# Sedna_Power_Board_v2.net
KiCad netlist of a schematic drawn in EAGLE
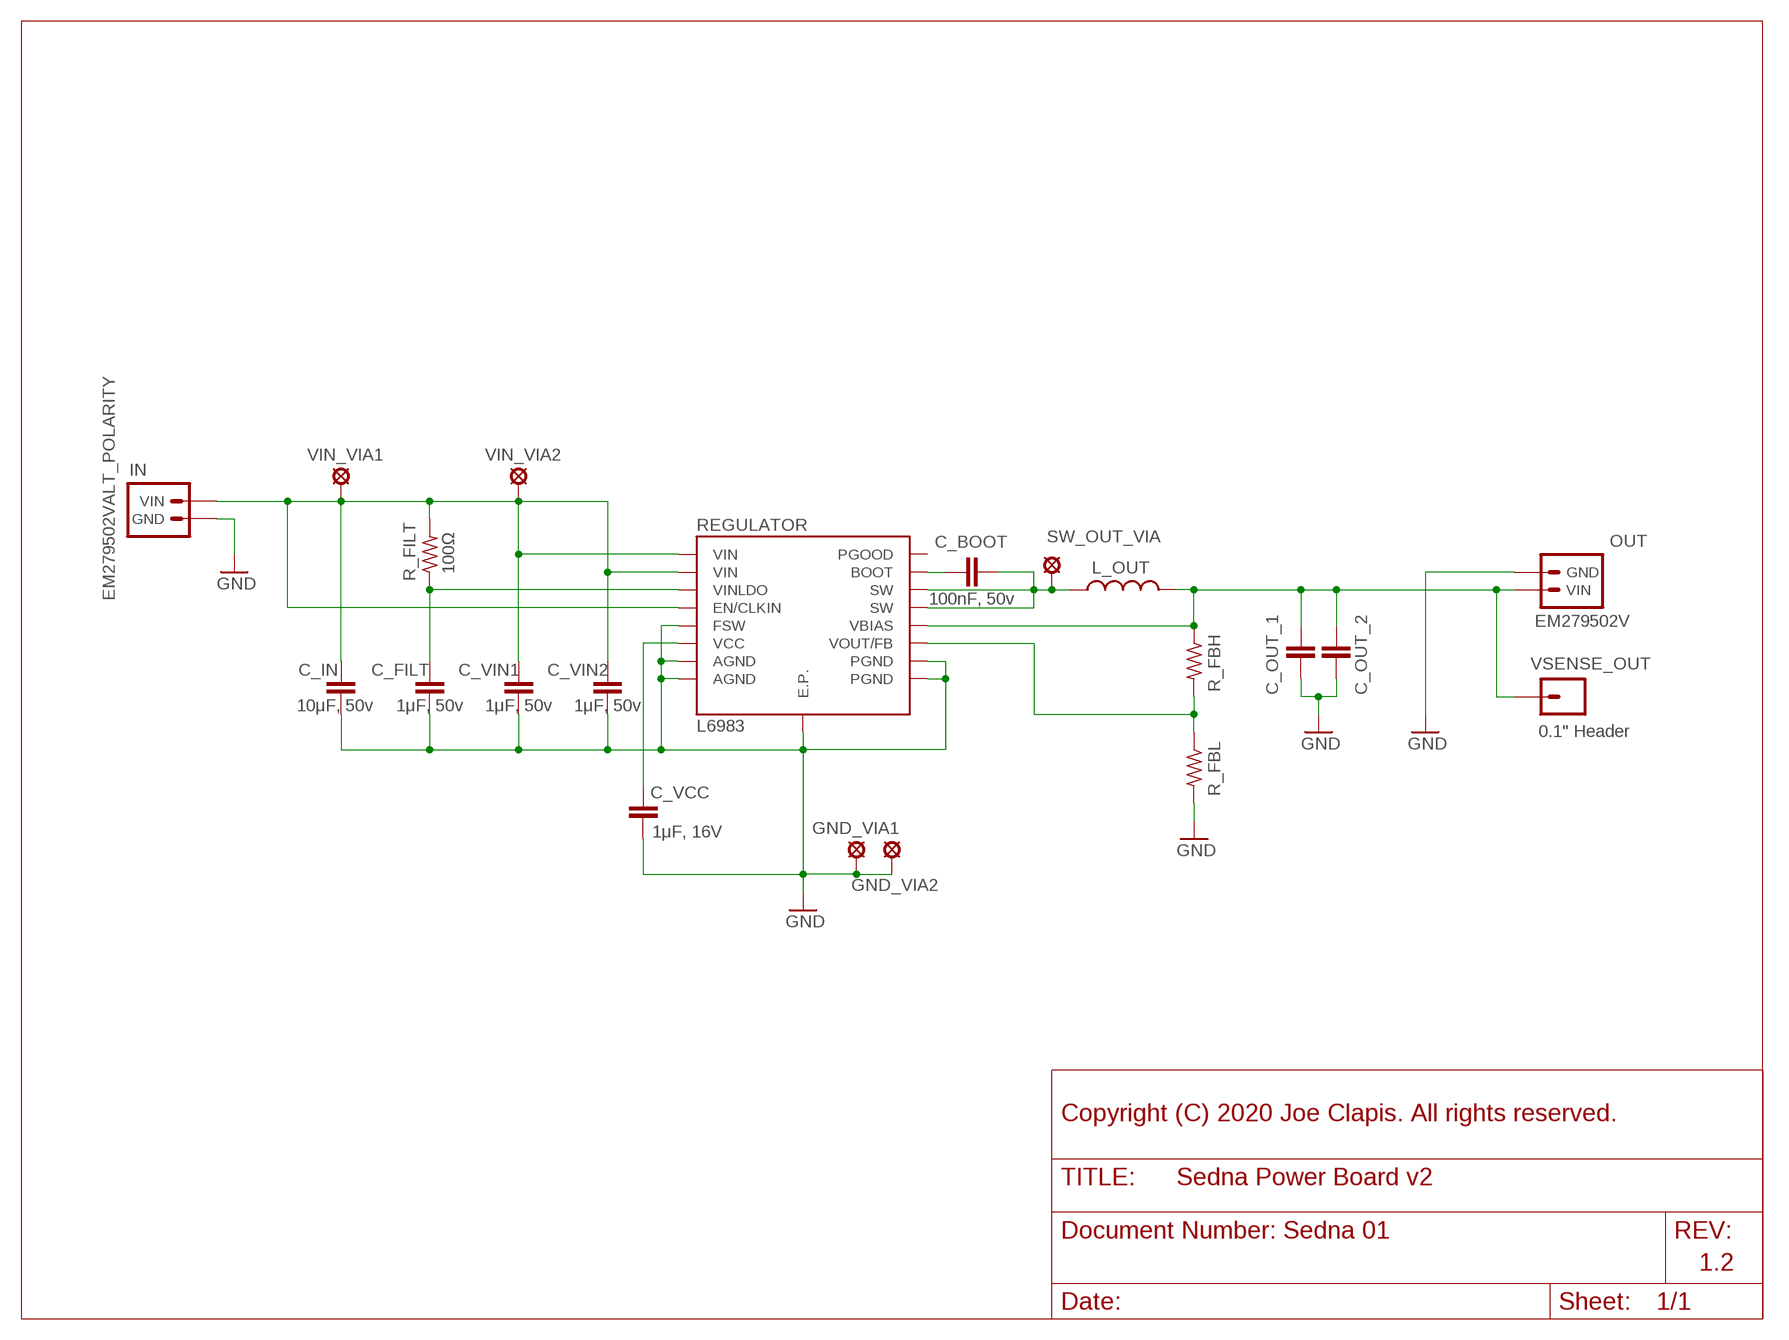
[diagram p0: schematic, sheet 1]

(export (version "E")
  (design (tool "Eeschema 10.0.6"))
  (components
    (comp (ref "C_BOOT")
      (value "100nF, 50v")
      (footprint "eagle-import:C0805")
      (libsource (lib "eagle-import") (part "C-EUC0805"))
    )
    (comp (ref "C_FILT")
      (value "1μF, 50v")
      (footprint "eagle-import:C0805")
      (libsource (lib "eagle-import") (part "C-EUC0805"))
    )
    (comp (ref "C_IN")
      (value "10μF, 50v")
      (footprint "eagle-import:C1206")
      (libsource (lib "eagle-import") (part "C-EUC1206"))
    )
    (comp (ref "C_OUT_1")
      (value "TDK_C2220_5750")
      (footprint "eagle-import:TDK_C2220_5750")
      (libsource (lib "eagle-import") (part "TDK_C2220_5750"))
    )
    (comp (ref "C_OUT_2")
      (value "TDK_C2220_5750")
      (footprint "eagle-import:TDK_C2220_5750")
      (libsource (lib "eagle-import") (part "TDK_C2220_5750"))
    )
    (comp (ref "C_VCC")
      (value "1μF, 16V")
      (footprint "eagle-import:C0805")
      (libsource (lib "eagle-import") (part "C-EUC0805"))
    )
    (comp (ref "C_VIN1")
      (value "1μF, 50v")
      (footprint "eagle-import:C0805")
      (libsource (lib "eagle-import") (part "C-EUC0805"))
    )
    (comp (ref "C_VIN2")
      (value "1μF, 50v")
      (footprint "eagle-import:C0805")
      (libsource (lib "eagle-import") (part "C-EUC0805"))
    )
    (comp (ref "GND_VIA1")
      (value "LSP13")
      (footprint "eagle-import:LSP13")
      (libsource (lib "eagle-import") (part "LSP13"))
    )
    (comp (ref "GND_VIA2")
      (value "LSP13")
      (footprint "eagle-import:LSP13")
      (libsource (lib "eagle-import") (part "LSP13"))
    )
    (comp (ref "IN")
      (value "EM279502VALT_POLARITY")
      (footprint "eagle-import:EM279502V")
      (libsource (lib "eagle-import") (part "EM279502VALT_POLARITY"))
    )
    (comp (ref "L_OUT")
      (value "PA4343_FP2")
      (footprint "eagle-import:PA4343_FP2")
      (libsource (lib "eagle-import") (part "PA4343_FP2"))
    )
    (comp (ref "OUT")
      (value "EM279502V")
      (footprint "eagle-import:EM279502V")
      (libsource (lib "eagle-import") (part "EM279502V"))
    )
    (comp (ref "REGULATOR")
      (value "L6983")
      (footprint "eagle-import:L6983")
      (fields (field (name "SPICEPREFIX") "X"))
      (libsource (lib "eagle-import") (part "L6983"))
    )
    (comp (ref "R_FBH")
      (value "R-US_R0805")
      (footprint "eagle-import:R0805")
      (libsource (lib "eagle-import") (part "R-US_R0805"))
    )
    (comp (ref "R_FBL")
      (value "R-US_R0805")
      (footprint "eagle-import:R0805")
      (libsource (lib "eagle-import") (part "R-US_R0805"))
    )
    (comp (ref "R_FILT")
      (value "100Ω")
      (footprint "eagle-import:R0805")
      (libsource (lib "eagle-import") (part "R-US_R0805"))
    )
    (comp (ref "SW_OUT_VIA")
      (value "LSP13")
      (footprint "eagle-import:LSP13")
      (libsource (lib "eagle-import") (part "LSP13"))
    )
    (comp (ref "VIN_VIA1")
      (value "LSP13")
      (footprint "eagle-import:LSP13")
      (libsource (lib "eagle-import") (part "LSP13"))
    )
    (comp (ref "VIN_VIA2")
      (value "LSP13")
      (footprint "eagle-import:LSP13")
      (libsource (lib "eagle-import") (part "LSP13"))
    )
    (comp (ref "VSENSE_OUT")
      (value "0.1\" Header")
      (footprint "eagle-import:1X01")
      (libsource (lib "eagle-import") (part "M01PTH"))
    )
  )
  (nets
    (net (code "1") (name "GND") (class "Default")
      (node (ref "C_FILT") (pin "2") (pinfunction "2_2") (pintype "passive"))
      (node (ref "C_IN") (pin "2") (pinfunction "2_2") (pintype "passive"))
      (node (ref "C_OUT_1") (pin "2") (pinfunction "2_2") (pintype "passive"))
      (node (ref "C_OUT_2") (pin "2") (pinfunction "2_2") (pintype "passive"))
      (node (ref "C_VCC") (pin "2") (pinfunction "2_2") (pintype "passive"))
      (node (ref "C_VIN1") (pin "2") (pinfunction "2_2") (pintype "passive"))
      (node (ref "C_VIN2") (pin "2") (pinfunction "2_2") (pintype "passive"))
      (node (ref "GND_VIA1") (pin "MP") (pinfunction "MP_MP") (pintype "passive"))
      (node (ref "GND_VIA2") (pin "MP") (pinfunction "MP_MP") (pintype "passive"))
      (node (ref "IN") (pin "1A") (pinfunction "GND_1A") (pintype "passive"))
      (node (ref "IN") (pin "1B") (pinfunction "GND_1B") (pintype "passive"))
      (node (ref "OUT") (pin "2A") (pinfunction "GND_2A") (pintype "passive"))
      (node (ref "OUT") (pin "2B") (pinfunction "GND_2B") (pintype "passive"))
      (node (ref "REGULATOR") (pin "10_AGND") (pinfunction "AGND_10_AGND") (pintype "power_in"))
      (node (ref "REGULATOR") (pin "13_PGND") (pinfunction "PGND_13_PGND") (pintype "power_in"))
      (node (ref "REGULATOR") (pin "16_PGND") (pinfunction "PGND_16_PGND") (pintype "power_in"))
      (node (ref "REGULATOR") (pin "3_AGND") (pinfunction "AGND_3_AGND") (pintype "power_in"))
      (node (ref "REGULATOR") (pin "8_FSW") (pinfunction "FSW_8_FSW") (pintype "output"))
      (node (ref "REGULATOR") (pin "E.P.") (pinfunction "E.P._E.P.") (pintype "power_in"))
      (node (ref "R_FBL") (pin "2") (pinfunction "2_2") (pintype "passive"))
    )
    (net (code "2") (name "Net-(C_BOOT-Pad2)") (class "Default")
      (node (ref "C_BOOT") (pin "2") (pinfunction "2_2") (pintype "passive"))
      (node (ref "L_OUT") (pin "1") (pinfunction "1_1") (pintype "passive"))
      (node (ref "REGULATOR") (pin "14_SW") (pinfunction "SW_14_SW") (pintype "power_in"))
      (node (ref "REGULATOR") (pin "15_SW") (pinfunction "SW_15_SW") (pintype "power_in"))
      (node (ref "SW_OUT_VIA") (pin "MP") (pinfunction "MP_MP") (pintype "passive"))
    )
    (net (code "3") (name "Net-(REGULATOR-BOOT)") (class "Default")
      (node (ref "C_BOOT") (pin "1") (pinfunction "1_1") (pintype "passive"))
      (node (ref "REGULATOR") (pin "11_BOOT") (pinfunction "BOOT_11_BOOT") (pintype "power_in"))
    )
    (net (code "4") (name "Net-(REGULATOR-EN{slash}CLKIN)") (class "Default")
      (node (ref "C_IN") (pin "1") (pinfunction "1_1") (pintype "passive"))
      (node (ref "C_VIN1") (pin "1") (pinfunction "1_1") (pintype "passive"))
      (node (ref "C_VIN2") (pin "1") (pinfunction "1_1") (pintype "passive"))
      (node (ref "IN") (pin "2A") (pinfunction "VIN_2A") (pintype "passive"))
      (node (ref "IN") (pin "2B") (pinfunction "VIN_2B") (pintype "passive"))
      (node (ref "REGULATOR") (pin "12_VIN") (pinfunction "VIN_12_VIN") (pintype "power_in"))
      (node (ref "REGULATOR") (pin "1_VIN") (pinfunction "VIN_1_VIN") (pintype "power_in"))
      (node (ref "REGULATOR") (pin "4_EN/CLKIN") (pinfunction "EN/CLKIN_4_EN/CLKIN") (pintype "input"))
      (node (ref "R_FILT") (pin "2") (pinfunction "2_2") (pintype "passive"))
      (node (ref "VIN_VIA1") (pin "MP") (pinfunction "MP_MP") (pintype "passive"))
      (node (ref "VIN_VIA2") (pin "MP") (pinfunction "MP_MP") (pintype "passive"))
    )
    (net (code "5") (name "Net-(REGULATOR-VBIAS)") (class "Default")
      (node (ref "C_OUT_1") (pin "1") (pinfunction "1_1") (pintype "passive"))
      (node (ref "C_OUT_2") (pin "1") (pinfunction "1_1") (pintype "passive"))
      (node (ref "L_OUT") (pin "2") (pinfunction "2_2") (pintype "passive"))
      (node (ref "OUT") (pin "1A") (pinfunction "VIN_1A") (pintype "passive"))
      (node (ref "OUT") (pin "1B") (pinfunction "VIN_1B") (pintype "passive"))
      (node (ref "REGULATOR") (pin "6_VBIAS") (pinfunction "VBIAS_6_VBIAS") (pintype "input"))
      (node (ref "R_FBH") (pin "1") (pinfunction "1_1") (pintype "passive"))
      (node (ref "VSENSE_OUT") (pin "1") (pinfunction "1_1") (pintype "passive"))
    )
    (net (code "6") (name "Net-(REGULATOR-VCC)") (class "Default")
      (node (ref "C_VCC") (pin "1") (pinfunction "1_1") (pintype "passive"))
      (node (ref "REGULATOR") (pin "9_VCC") (pinfunction "VCC_9_VCC") (pintype "power_in"))
    )
    (net (code "7") (name "Net-(REGULATOR-VINLDO)") (class "Default")
      (node (ref "C_FILT") (pin "1") (pinfunction "1_1") (pintype "passive"))
      (node (ref "REGULATOR") (pin "2_VINLDO") (pinfunction "VINLDO_2_VINLDO") (pintype "power_in"))
      (node (ref "R_FILT") (pin "1") (pinfunction "1_1") (pintype "passive"))
    )
    (net (code "8") (name "Net-(REGULATOR-VOUT{slash}FB)") (class "Default")
      (node (ref "REGULATOR") (pin "7_FB/VOUT") (pinfunction "VOUT/FB_7_FB/VOUT") (pintype "input"))
      (node (ref "R_FBH") (pin "2") (pinfunction "2_2") (pintype "passive"))
      (node (ref "R_FBL") (pin "1") (pinfunction "1_1") (pintype "passive"))
    )
    (net (code "9") (name "unconnected-(REGULATOR-PGOOD-Pad5_PGOOD)") (class "Default")
      (node (ref "REGULATOR") (pin "5_PGOOD") (pinfunction "PGOOD_5_PGOOD") (pintype "output"))
    )
  )
)
